# DDS_Tone_Shield.net
KiCad netlist of a schematic drawn in EAGLE
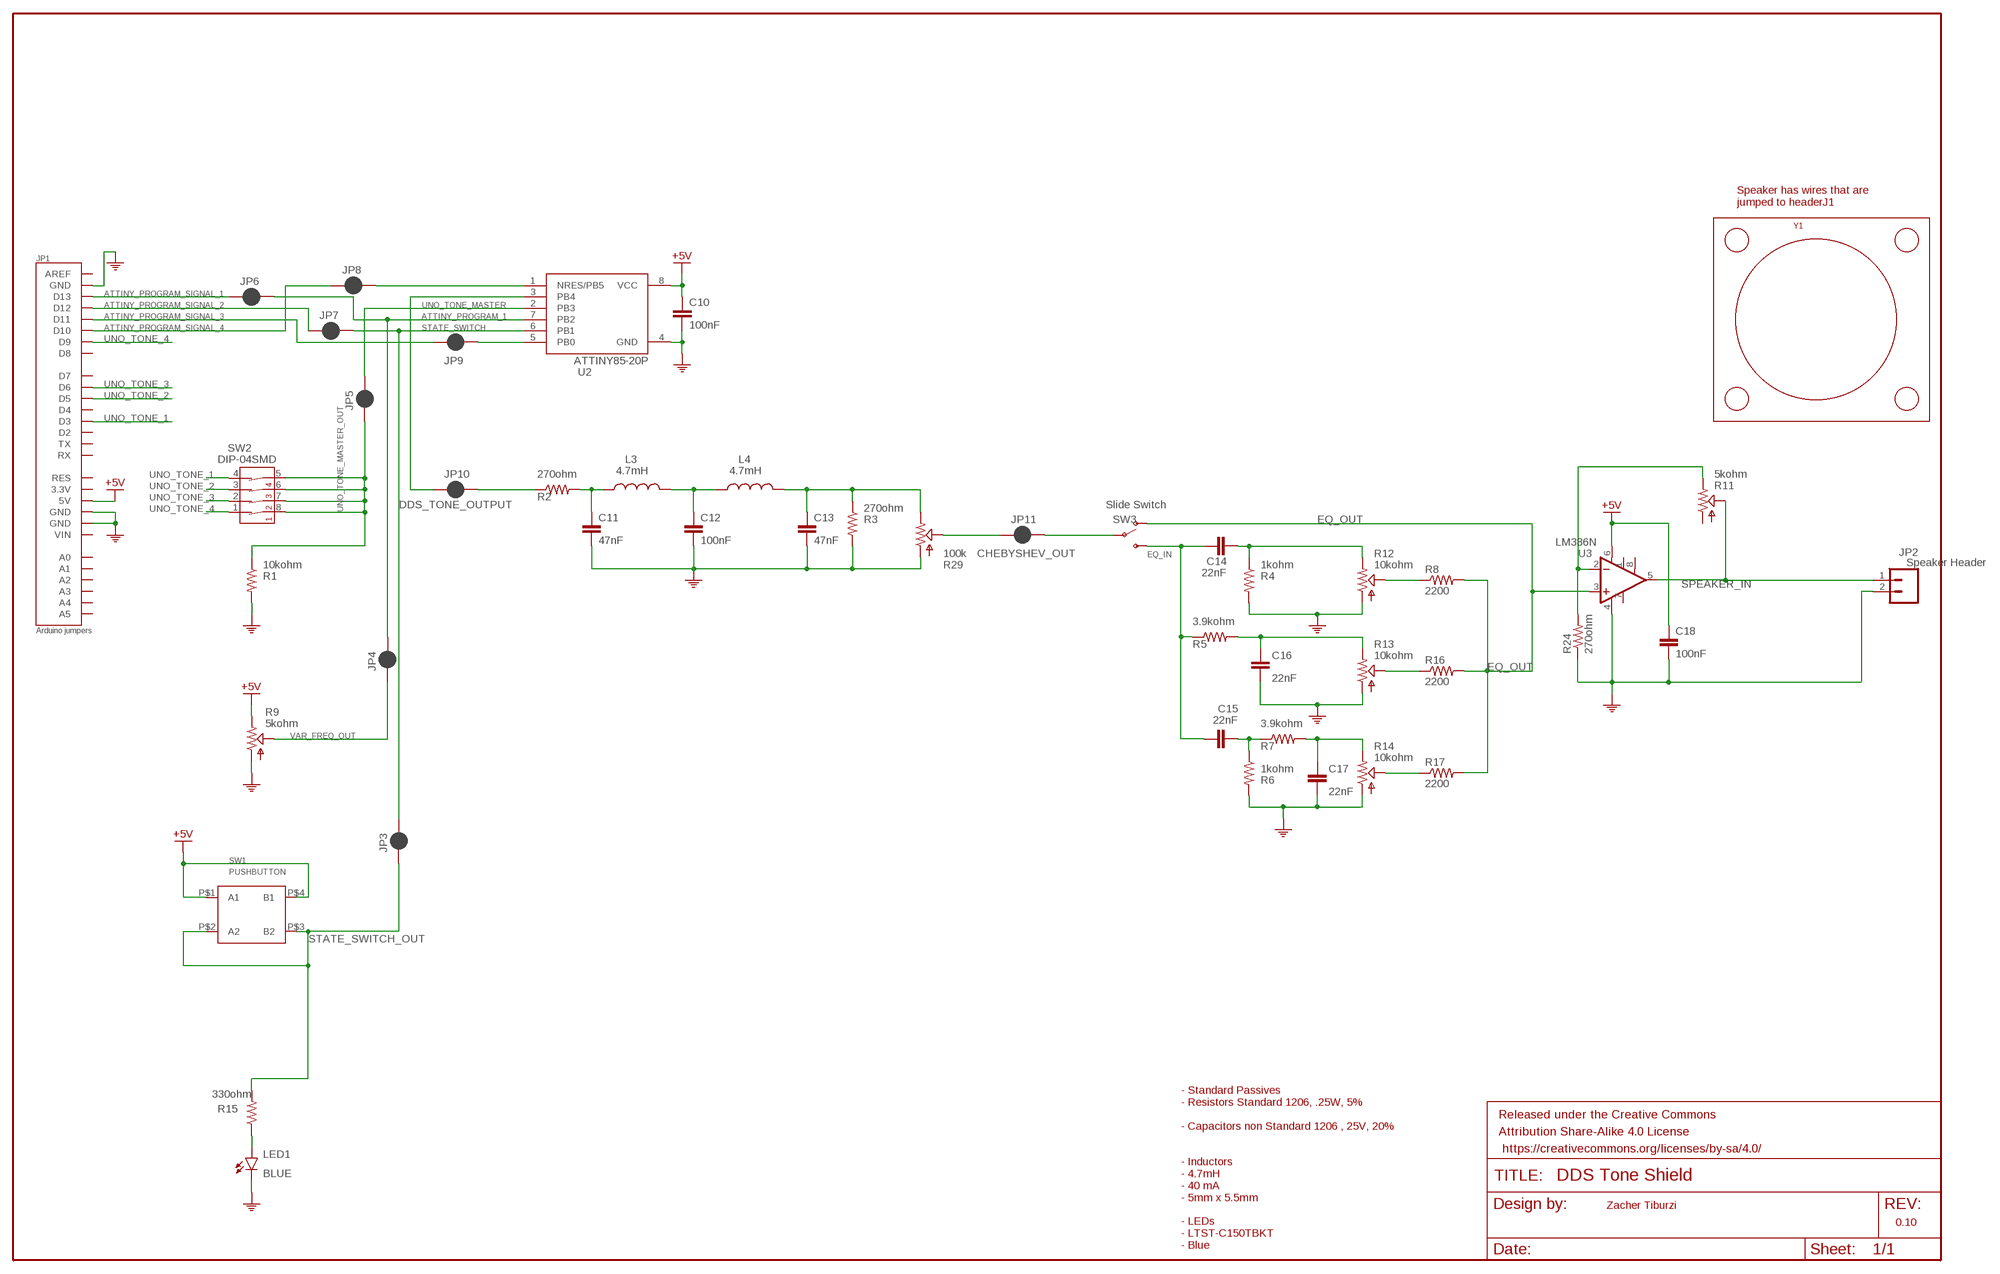
[diagram p0: schematic, sheet 1]

(export (version "E")
  (design (tool "Eeschema 10.0.6"))
  (components
    (comp (ref "C10")
      (value "100nF")
      (footprint "eagle-import:EIA3216")
      (libsource (lib "eagle-import") (part "CAP1206"))
    )
    (comp (ref "C11")
      (value "47nF")
      (footprint "eagle-import:EIA3216")
      (libsource (lib "eagle-import") (part "CAP1206"))
    )
    (comp (ref "C12")
      (value "100nF")
      (footprint "eagle-import:EIA3216")
      (libsource (lib "eagle-import") (part "CAP1206"))
    )
    (comp (ref "C13")
      (value "47nF")
      (footprint "eagle-import:EIA3216")
      (libsource (lib "eagle-import") (part "CAP1206"))
    )
    (comp (ref "C14")
      (value "22nF")
      (footprint "eagle-import:EIA3216")
      (libsource (lib "eagle-import") (part "CAP1206"))
    )
    (comp (ref "C15")
      (value "22nF")
      (footprint "eagle-import:EIA3216")
      (libsource (lib "eagle-import") (part "CAP1206"))
    )
    (comp (ref "C16")
      (value "22nF")
      (footprint "eagle-import:EIA3216")
      (libsource (lib "eagle-import") (part "CAP1206"))
    )
    (comp (ref "C17")
      (value "22nF")
      (footprint "eagle-import:EIA3216")
      (libsource (lib "eagle-import") (part "CAP1206"))
    )
    (comp (ref "C18")
      (value "100nF")
      (footprint "eagle-import:EIA3216")
      (libsource (lib "eagle-import") (part "CAP1206"))
    )
    (comp (ref "FRAME2")
      (value "FRAME-LEDGER")
      (footprint "eagle-import:CREATIVE_COMMONS")
      (libsource (lib "eagle-import") (part "FRAME-LEDGER"))
    )
    (comp (ref "JP1")
      (value "Arduino jumpers")
      (footprint "eagle-import:DUEMILANOVE_SHIELD")
      (libsource (lib "eagle-import") (part "ARDUINO_SHIELD"))
    )
    (comp (ref "JP2")
      (value "Speaker Header")
      (footprint "eagle-import:1X02")
      (libsource (lib "eagle-import") (part "CONN_02"))
    )
    (comp (ref "JP3")
      (value "JUMPER-SMT_2_NC_PASTE_SILK")
      (footprint "eagle-import:SMT-JUMPER_2_NC_PASTE_SILK")
      (libsource (lib "eagle-import") (part "JUMPER-SMT_2_NC_PASTE_SILK"))
    )
    (comp (ref "JP4")
      (value "JUMPER-SMT_2_NC_PASTE_SILK")
      (footprint "eagle-import:SMT-JUMPER_2_NC_PASTE_SILK")
      (libsource (lib "eagle-import") (part "JUMPER-SMT_2_NC_PASTE_SILK"))
    )
    (comp (ref "JP5")
      (value "JUMPER-SMT_2_NC_PASTE_SILK")
      (footprint "eagle-import:SMT-JUMPER_2_NC_PASTE_SILK")
      (libsource (lib "eagle-import") (part "JUMPER-SMT_2_NC_PASTE_SILK"))
    )
    (comp (ref "JP6")
      (value "JUMPER-SMT_2_NC_PASTE_SILK")
      (footprint "eagle-import:SMT-JUMPER_2_NC_PASTE_SILK")
      (libsource (lib "eagle-import") (part "JUMPER-SMT_2_NC_PASTE_SILK"))
    )
    (comp (ref "JP7")
      (value "JUMPER-SMT_2_NC_PASTE_SILK")
      (footprint "eagle-import:SMT-JUMPER_2_NC_PASTE_SILK")
      (libsource (lib "eagle-import") (part "JUMPER-SMT_2_NC_PASTE_SILK"))
    )
    (comp (ref "JP8")
      (value "JUMPER-SMT_2_NC_PASTE_SILK")
      (footprint "eagle-import:SMT-JUMPER_2_NC_PASTE_SILK")
      (libsource (lib "eagle-import") (part "JUMPER-SMT_2_NC_PASTE_SILK"))
    )
    (comp (ref "JP9")
      (value "JUMPER-SMT_2_NC_PASTE_SILK")
      (footprint "eagle-import:SMT-JUMPER_2_NC_PASTE_SILK")
      (libsource (lib "eagle-import") (part "JUMPER-SMT_2_NC_PASTE_SILK"))
    )
    (comp (ref "JP10")
      (value "JUMPER-SMT_2_NC_PASTE_SILK")
      (footprint "eagle-import:SMT-JUMPER_2_NC_PASTE_SILK")
      (libsource (lib "eagle-import") (part "JUMPER-SMT_2_NC_PASTE_SILK"))
    )
    (comp (ref "JP11")
      (value "JUMPER-SMT_2_NC_PASTE_SILK")
      (footprint "eagle-import:SMT-JUMPER_2_NC_PASTE_SILK")
      (libsource (lib "eagle-import") (part "JUMPER-SMT_2_NC_PASTE_SILK"))
    )
    (comp (ref "L3")
      (value "4.7mH")
      (footprint "eagle-import:SDR0503-472JL")
      (libsource (lib "eagle-import") (part "INDUCTOR_"))
    )
    (comp (ref "L4")
      (value "4.7mH")
      (footprint "eagle-import:SDR0503-472JL")
      (libsource (lib "eagle-import") (part "INDUCTOR_"))
    )
    (comp (ref "LED1")
      (value "BLUE")
      (footprint "eagle-import:LED-1206")
      (libsource (lib "eagle-import") (part "LED-BLUE1206"))
    )
    (comp (ref "R1")
      (value "10kohm")
      (footprint "eagle-import:1206")
      (libsource (lib "eagle-import") (part "RESISTOR1206"))
    )
    (comp (ref "R2")
      (value "270ohm")
      (footprint "eagle-import:1206")
      (libsource (lib "eagle-import") (part "RESISTOR1206"))
    )
    (comp (ref "R3")
      (value "270ohm")
      (footprint "eagle-import:1206")
      (libsource (lib "eagle-import") (part "RESISTOR1206"))
    )
    (comp (ref "R4")
      (value "1kohm")
      (footprint "eagle-import:1206")
      (libsource (lib "eagle-import") (part "RESISTOR1206"))
    )
    (comp (ref "R5")
      (value "3.9kohm")
      (footprint "eagle-import:1206")
      (libsource (lib "eagle-import") (part "RESISTOR1206"))
    )
    (comp (ref "R6")
      (value "1kohm")
      (footprint "eagle-import:1206")
      (libsource (lib "eagle-import") (part "RESISTOR1206"))
    )
    (comp (ref "R7")
      (value "3.9kohm")
      (footprint "eagle-import:1206")
      (libsource (lib "eagle-import") (part "RESISTOR1206"))
    )
    (comp (ref "R8")
      (value "2200")
      (footprint "eagle-import:1206")
      (libsource (lib "eagle-import") (part "RESISTOR1206"))
    )
    (comp (ref "R9")
      (value "5kohm")
      (footprint "eagle-import:RK09K_RK09D_SERIES")
      (libsource (lib "eagle-import") (part "POT1"))
    )
    (comp (ref "R11")
      (value "5kohm")
      (footprint "eagle-import:RK09K_RK09D_SERIES")
      (libsource (lib "eagle-import") (part "POT1"))
    )
    (comp (ref "R12")
      (value "10kohm")
      (footprint "eagle-import:RK09K_RK09D_SERIES")
      (libsource (lib "eagle-import") (part "POT1"))
    )
    (comp (ref "R13")
      (value "10kohm")
      (footprint "eagle-import:RK09K_RK09D_SERIES")
      (libsource (lib "eagle-import") (part "POT1"))
    )
    (comp (ref "R14")
      (value "10kohm")
      (footprint "eagle-import:RK09K_RK09D_SERIES")
      (libsource (lib "eagle-import") (part "POT1"))
    )
    (comp (ref "R15")
      (value "330ohm")
      (footprint "eagle-import:1206")
      (libsource (lib "eagle-import") (part "RESISTOR1206"))
    )
    (comp (ref "R16")
      (value "2200")
      (footprint "eagle-import:1206")
      (libsource (lib "eagle-import") (part "RESISTOR1206"))
    )
    (comp (ref "R17")
      (value "2200")
      (footprint "eagle-import:1206")
      (libsource (lib "eagle-import") (part "RESISTOR1206"))
    )
    (comp (ref "R24")
      (value "270ohm")
      (footprint "eagle-import:1206")
      (libsource (lib "eagle-import") (part "RESISTOR1206"))
    )
    (comp (ref "R29")
      (value "100k")
      (footprint "eagle-import:RK09K_RK09D_SERIES")
      (libsource (lib "eagle-import") (part "POT1"))
    )
    (comp (ref "SW1")
      (value "PUSHBUTTON")
      (footprint "eagle-import:3CSH9_MEC_PUSHBUTTON")
      (libsource (lib "eagle-import") (part "PUSHBUTTON"))
    )
    (comp (ref "SW2")
      (value "DIP-04SMD")
      (footprint "eagle-import:DIPSWITCH-04-SMD")
      (libsource (lib "eagle-import") (part "DIP-04SMD"))
    )
    (comp (ref "SW3")
      (value "Slide Switch")
      (footprint "eagle-import:JS102011SAQN")
      (libsource (lib "eagle-import") (part "SWITCH-SPDT"))
    )
    (comp (ref "U2")
      (value "ATTINY85-20P")
      (footprint "eagle-import:PDIP08_300MIL")
      (libsource (lib "eagle-import") (part "ATTINY85P-20"))
    )
    (comp (ref "U3")
      (value "LM386N")
      (footprint "eagle-import:DIP08")
      (libsource (lib "eagle-import") (part "LM386"))
    )
    (comp (ref "Y1")
      (value "Speaker")
      (footprint "eagle-import:CSS-40408N")
      (libsource (lib "eagle-import") (part "SPEAKER"))
    )
  )
  (nets
    (net (code "1") (name "/ATTINY_PROGRAM_1") (class "Default")
      (node (ref "JP4") (pin "2") (pinfunction "2_2") (pintype "passive"))
      (node (ref "JP6") (pin "2") (pinfunction "2_2") (pintype "passive"))
      (node (ref "U2") (pin "7") (pinfunction "PB2_7") (pintype "bidirectional"))
    )
    (net (code "2") (name "/ATTINY_PROGRAM_SIGNAL_1") (class "Default")
      (node (ref "JP1") (pin "D13") (pinfunction "D13_D13") (pintype "bidirectional"))
      (node (ref "JP6") (pin "1") (pinfunction "1_1") (pintype "passive"))
    )
    (net (code "3") (name "/ATTINY_PROGRAM_SIGNAL_2") (class "Default")
      (node (ref "JP1") (pin "D12") (pinfunction "D12_D12") (pintype "bidirectional"))
      (node (ref "JP7") (pin "1") (pinfunction "1_1") (pintype "passive"))
    )
    (net (code "4") (name "/ATTINY_PROGRAM_SIGNAL_3") (class "Default")
      (node (ref "JP1") (pin "D11") (pinfunction "D11_D11") (pintype "bidirectional"))
      (node (ref "JP9") (pin "1") (pinfunction "1_1") (pintype "passive"))
    )
    (net (code "5") (name "/ATTINY_PROGRAM_SIGNAL_4") (class "Default")
      (node (ref "JP1") (pin "D10") (pinfunction "D10_D10") (pintype "bidirectional"))
      (node (ref "JP8") (pin "1") (pinfunction "1_1") (pintype "passive"))
    )
    (net (code "6") (name "/CHEBYSHEV_OUT") (class "Default")
      (node (ref "JP11") (pin "1") (pinfunction "1_1") (pintype "passive"))
      (node (ref "R29") (pin "P$2") (pinfunction "S_P$2") (pintype "passive"))
    )
    (net (code "7") (name "/DDS_TONE_OUTPUT") (class "Default")
      (node (ref "JP10") (pin "1") (pinfunction "1_1") (pintype "passive"))
      (node (ref "U2") (pin "3") (pinfunction "PB4_3") (pintype "bidirectional"))
    )
    (net (code "8") (name "/EQ_IN") (class "Default")
      (node (ref "C14") (pin "A") (pinfunction "1_A") (pintype "passive"))
      (node (ref "C15") (pin "A") (pinfunction "1_A") (pintype "passive"))
      (node (ref "R5") (pin "1") (pinfunction "1_1") (pintype "passive"))
      (node (ref "SW3") (pin "P$1") (pinfunction "S_P$1") (pintype "passive"))
    )
    (net (code "9") (name "/EQ_OUT") (class "Default")
      (node (ref "R16") (pin "2") (pinfunction "2_2") (pintype "passive"))
      (node (ref "R17") (pin "2") (pinfunction "2_2") (pintype "passive"))
      (node (ref "R8") (pin "2") (pinfunction "2_2") (pintype "passive"))
      (node (ref "SW3") (pin "P$2") (pinfunction "O_P$2") (pintype "passive"))
      (node (ref "U3") (pin "3") (pinfunction "+IN_3") (pintype "input"))
    )
    (net (code "10") (name "/SPEAKER_IN") (class "Default")
      (node (ref "JP2") (pin "1") (pinfunction "1_1") (pintype "passive"))
      (node (ref "R11") (pin "P$2") (pinfunction "S_P$2") (pintype "passive"))
      (node (ref "U3") (pin "5") (pinfunction "OUT_5") (pintype "output"))
    )
    (net (code "11") (name "/STATE_SWITCH") (class "Default")
      (node (ref "JP3") (pin "2") (pinfunction "2_2") (pintype "passive"))
      (node (ref "JP7") (pin "2") (pinfunction "2_2") (pintype "passive"))
      (node (ref "U2") (pin "6") (pinfunction "PB1_6") (pintype "bidirectional"))
    )
    (net (code "12") (name "/STATE_SWITCH_OUT") (class "Default")
      (node (ref "JP3") (pin "1") (pinfunction "1_1") (pintype "passive"))
      (node (ref "R15") (pin "2") (pinfunction "2_2") (pintype "passive"))
      (node (ref "SW1") (pin "P$2") (pinfunction "A2_P$2") (pintype "bidirectional"))
      (node (ref "SW1") (pin "P$3") (pinfunction "B2_P$3") (pintype "bidirectional"))
    )
    (net (code "13") (name "/UNO_TONE_1") (class "Default")
      (node (ref "JP1") (pin "D3") (pinfunction "D3_D3") (pintype "bidirectional"))
      (node (ref "SW2") (pin "4") (pinfunction "4A_4") (pintype "bidirectional"))
    )
    (net (code "14") (name "/UNO_TONE_2") (class "Default")
      (node (ref "JP1") (pin "D5") (pinfunction "D5_D5") (pintype "bidirectional"))
      (node (ref "SW2") (pin "3") (pinfunction "3A_3") (pintype "bidirectional"))
    )
    (net (code "15") (name "/UNO_TONE_3") (class "Default")
      (node (ref "JP1") (pin "D6") (pinfunction "D6_D6") (pintype "bidirectional"))
      (node (ref "SW2") (pin "2") (pinfunction "2A_2") (pintype "bidirectional"))
    )
    (net (code "16") (name "/UNO_TONE_4") (class "Default")
      (node (ref "JP1") (pin "D9") (pinfunction "D9_D9") (pintype "bidirectional"))
      (node (ref "SW2") (pin "1") (pinfunction "1A_1") (pintype "bidirectional"))
    )
    (net (code "17") (name "/UNO_TONE_MASTER") (class "Default")
      (node (ref "JP5") (pin "2") (pinfunction "2_2") (pintype "passive"))
      (node (ref "U2") (pin "2") (pinfunction "PB3_2") (pintype "bidirectional"))
    )
    (net (code "18") (name "/UNO_TONE_MASTER_OUT") (class "Default")
      (node (ref "JP5") (pin "1") (pinfunction "1_1") (pintype "passive"))
      (node (ref "R1") (pin "1") (pinfunction "1_1") (pintype "passive"))
      (node (ref "SW2") (pin "5") (pinfunction "4B_5") (pintype "bidirectional"))
      (node (ref "SW2") (pin "6") (pinfunction "3B_6") (pintype "bidirectional"))
      (node (ref "SW2") (pin "7") (pinfunction "2B_7") (pintype "bidirectional"))
      (node (ref "SW2") (pin "8") (pinfunction "1B_8") (pintype "bidirectional"))
    )
    (net (code "19") (name "/VAR_FREQ_OUT") (class "Default")
      (node (ref "JP4") (pin "1") (pinfunction "1_1") (pintype "passive"))
      (node (ref "R9") (pin "P$2") (pinfunction "S_P$2") (pintype "passive"))
    )
    (net (code "20") (name "5V") (class "Default")
      (node (ref "C10") (pin "A") (pinfunction "1_A") (pintype "passive"))
      (node (ref "C18") (pin "A") (pinfunction "1_A") (pintype "passive"))
      (node (ref "JP1") (pin "5V") (pinfunction "5V_5V") (pintype "bidirectional"))
      (node (ref "R9") (pin "P$3") (pinfunction "E_P$3") (pintype "passive"))
      (node (ref "SW1") (pin "P$1") (pinfunction "A1_P$1") (pintype "bidirectional"))
      (node (ref "SW1") (pin "P$4") (pinfunction "B1_P$4") (pintype "bidirectional"))
      (node (ref "U2") (pin "8") (pinfunction "VCC_8") (pintype "power_in"))
      (node (ref "U3") (pin "6") (pinfunction "V+_6") (pintype "power_in"))
    )
    (net (code "21") (name "GND_US") (class "Default")
      (node (ref "C10") (pin "C") (pinfunction "2_C") (pintype "passive"))
      (node (ref "C11") (pin "C") (pinfunction "2_C") (pintype "passive"))
      (node (ref "C12") (pin "C") (pinfunction "2_C") (pintype "passive"))
      (node (ref "C13") (pin "C") (pinfunction "2_C") (pintype "passive"))
      (node (ref "C16") (pin "C") (pinfunction "2_C") (pintype "passive"))
      (node (ref "C17") (pin "C") (pinfunction "2_C") (pintype "passive"))
      (node (ref "C18") (pin "C") (pinfunction "2_C") (pintype "passive"))
      (node (ref "JP1") (pin "GND@0") (pinfunction "GND_GND@0") (pintype "bidirectional"))
      (node (ref "JP1") (pin "GND@1") (pinfunction "GND_GND@1") (pintype "bidirectional"))
      (node (ref "JP1") (pin "GND@2") (pinfunction "GND_GND@2") (pintype "bidirectional"))
      (node (ref "JP2") (pin "2") (pinfunction "2_2") (pintype "passive"))
      (node (ref "LED1") (pin "C") (pinfunction "C_C") (pintype "passive"))
      (node (ref "R1") (pin "2") (pinfunction "2_2") (pintype "passive"))
      (node (ref "R12") (pin "P$1") (pinfunction "A_P$1") (pintype "passive"))
      (node (ref "R13") (pin "P$1") (pinfunction "A_P$1") (pintype "passive"))
      (node (ref "R14") (pin "P$1") (pinfunction "A_P$1") (pintype "passive"))
      (node (ref "R24") (pin "1") (pinfunction "1_1") (pintype "passive"))
      (node (ref "R29") (pin "P$1") (pinfunction "A_P$1") (pintype "passive"))
      (node (ref "R3") (pin "2") (pinfunction "2_2") (pintype "passive"))
      (node (ref "R4") (pin "2") (pinfunction "2_2") (pintype "passive"))
      (node (ref "R6") (pin "2") (pinfunction "2_2") (pintype "passive"))
      (node (ref "R9") (pin "P$1") (pinfunction "A_P$1") (pintype "passive"))
      (node (ref "U2") (pin "4") (pinfunction "GND_4") (pintype "power_in"))
      (node (ref "U3") (pin "4") (pinfunction "V-_4") (pintype "power_in"))
    )
    (net (code "22") (name "Net-(C11-1)") (class "Default")
      (node (ref "C11") (pin "A") (pinfunction "1_A") (pintype "passive"))
      (node (ref "L3") (pin "P$1") (pinfunction "1_P$1") (pintype "passive"))
      (node (ref "R2") (pin "2") (pinfunction "2_2") (pintype "passive"))
    )
    (net (code "23") (name "Net-(C12-1)") (class "Default")
      (node (ref "C12") (pin "A") (pinfunction "1_A") (pintype "passive"))
      (node (ref "L3") (pin "P$2") (pinfunction "2_P$2") (pintype "passive"))
      (node (ref "L4") (pin "P$1") (pinfunction "1_P$1") (pintype "passive"))
    )
    (net (code "24") (name "Net-(C13-1)") (class "Default")
      (node (ref "C13") (pin "A") (pinfunction "1_A") (pintype "passive"))
      (node (ref "L4") (pin "P$2") (pinfunction "2_P$2") (pintype "passive"))
      (node (ref "R29") (pin "P$3") (pinfunction "E_P$3") (pintype "passive"))
      (node (ref "R3") (pin "1") (pinfunction "1_1") (pintype "passive"))
    )
    (net (code "25") (name "Net-(C14-2)") (class "Default")
      (node (ref "C14") (pin "C") (pinfunction "2_C") (pintype "passive"))
      (node (ref "R12") (pin "P$3") (pinfunction "E_P$3") (pintype "passive"))
      (node (ref "R4") (pin "1") (pinfunction "1_1") (pintype "passive"))
    )
    (net (code "26") (name "Net-(C15-2)") (class "Default")
      (node (ref "C15") (pin "C") (pinfunction "2_C") (pintype "passive"))
      (node (ref "R6") (pin "1") (pinfunction "1_1") (pintype "passive"))
      (node (ref "R7") (pin "1") (pinfunction "1_1") (pintype "passive"))
    )
    (net (code "27") (name "Net-(C16-1)") (class "Default")
      (node (ref "C16") (pin "A") (pinfunction "1_A") (pintype "passive"))
      (node (ref "R13") (pin "P$3") (pinfunction "E_P$3") (pintype "passive"))
      (node (ref "R5") (pin "2") (pinfunction "2_2") (pintype "passive"))
    )
    (net (code "28") (name "Net-(C17-1)") (class "Default")
      (node (ref "C17") (pin "A") (pinfunction "1_A") (pintype "passive"))
      (node (ref "R14") (pin "P$3") (pinfunction "E_P$3") (pintype "passive"))
      (node (ref "R7") (pin "2") (pinfunction "2_2") (pintype "passive"))
    )
    (net (code "29") (name "Net-(JP10-Pad2)") (class "Default")
      (node (ref "JP10") (pin "2") (pinfunction "2_2") (pintype "passive"))
      (node (ref "R2") (pin "1") (pinfunction "1_1") (pintype "passive"))
    )
    (net (code "30") (name "Net-(LED1-PadA)") (class "Default")
      (node (ref "LED1") (pin "A") (pinfunction "A_A") (pintype "passive"))
      (node (ref "R15") (pin "1") (pinfunction "1_1") (pintype "passive"))
    )
    (net (code "31") (name "Net-(R11-E)") (class "Default")
      (node (ref "R11") (pin "P$3") (pinfunction "E_P$3") (pintype "passive"))
      (node (ref "R24") (pin "2") (pinfunction "2_2") (pintype "passive"))
      (node (ref "U3") (pin "2") (pinfunction "-IN_2") (pintype "input"))
    )
    (net (code "32") (name "Net-(R12-S)") (class "Default")
      (node (ref "R12") (pin "P$2") (pinfunction "S_P$2") (pintype "passive"))
      (node (ref "R8") (pin "1") (pinfunction "1_1") (pintype "passive"))
    )
    (net (code "33") (name "Net-(R13-S)") (class "Default")
      (node (ref "R13") (pin "P$2") (pinfunction "S_P$2") (pintype "passive"))
      (node (ref "R16") (pin "1") (pinfunction "1_1") (pintype "passive"))
    )
    (net (code "34") (name "Net-(R14-S)") (class "Default")
      (node (ref "R14") (pin "P$2") (pinfunction "S_P$2") (pintype "passive"))
      (node (ref "R17") (pin "1") (pinfunction "1_1") (pintype "passive"))
    )
    (net (code "35") (name "Net-(SW3-P)") (class "Default")
      (node (ref "JP11") (pin "2") (pinfunction "2_2") (pintype "passive"))
      (node (ref "SW3") (pin "P$3") (pinfunction "P_P$3") (pintype "passive"))
    )
    (net (code "36") (name "Net-(U2-NRES{slash}PB5)") (class "Default")
      (node (ref "JP8") (pin "2") (pinfunction "2_2") (pintype "passive"))
      (node (ref "U2") (pin "1") (pinfunction "NRES/PB5_1") (pintype "bidirectional"))
    )
    (net (code "37") (name "Net-(U2-PB0)") (class "Default")
      (node (ref "JP9") (pin "2") (pinfunction "2_2") (pintype "passive"))
      (node (ref "U2") (pin "5") (pinfunction "PB0_5") (pintype "bidirectional"))
    )
    (net (code "38") (name "unconnected-(JP1-Pad3.3V)") (class "Default")
      (node (ref "JP1") (pin "3.3V") (pinfunction "3.3V_3.3V") (pintype "bidirectional"))
    )
    (net (code "39") (name "unconnected-(JP1-PadA0)") (class "Default")
      (node (ref "JP1") (pin "A0") (pinfunction "A0_A0") (pintype "bidirectional"))
    )
    (net (code "40") (name "unconnected-(JP1-PadA1)") (class "Default")
      (node (ref "JP1") (pin "A1") (pinfunction "A1_A1") (pintype "bidirectional"))
    )
    (net (code "41") (name "unconnected-(JP1-PadA2)") (class "Default")
      (node (ref "JP1") (pin "A2") (pinfunction "A2_A2") (pintype "bidirectional"))
    )
    (net (code "42") (name "unconnected-(JP1-PadA3)") (class "Default")
      (node (ref "JP1") (pin "A3") (pinfunction "A3_A3") (pintype "bidirectional"))
    )
    (net (code "43") (name "unconnected-(JP1-PadA4)") (class "Default")
      (node (ref "JP1") (pin "A4") (pinfunction "A4_A4") (pintype "bidirectional"))
    )
    (net (code "44") (name "unconnected-(JP1-PadA5)") (class "Default")
      (node (ref "JP1") (pin "A5") (pinfunction "A5_A5") (pintype "bidirectional"))
    )
    (net (code "45") (name "unconnected-(JP1-PadAREF)") (class "Default")
      (node (ref "JP1") (pin "AREF") (pinfunction "AREF_AREF") (pintype "bidirectional"))
    )
    (net (code "46") (name "unconnected-(JP1-PadD2)") (class "Default")
      (node (ref "JP1") (pin "D2") (pinfunction "D2_D2") (pintype "bidirectional"))
    )
    (net (code "47") (name "unconnected-(JP1-PadD4)") (class "Default")
      (node (ref "JP1") (pin "D4") (pinfunction "D4_D4") (pintype "bidirectional"))
    )
    (net (code "48") (name "unconnected-(JP1-PadD7)") (class "Default")
      (node (ref "JP1") (pin "D7") (pinfunction "D7_D7") (pintype "bidirectional"))
    )
    (net (code "49") (name "unconnected-(JP1-PadD8)") (class "Default")
      (node (ref "JP1") (pin "D8") (pinfunction "D8_D8") (pintype "bidirectional"))
    )
    (net (code "50") (name "unconnected-(JP1-PadRES)") (class "Default")
      (node (ref "JP1") (pin "RES") (pinfunction "RES_RES") (pintype "bidirectional"))
    )
    (net (code "51") (name "unconnected-(JP1-PadRX)") (class "Default")
      (node (ref "JP1") (pin "RX") (pinfunction "RX_RX") (pintype "bidirectional"))
    )
    (net (code "52") (name "unconnected-(JP1-PadTX)") (class "Default")
      (node (ref "JP1") (pin "TX") (pinfunction "TX_TX") (pintype "bidirectional"))
    )
    (net (code "53") (name "unconnected-(JP1-PadVIN)") (class "Default")
      (node (ref "JP1") (pin "VIN") (pinfunction "VIN_VIN") (pintype "bidirectional"))
    )
    (net (code "54") (name "unconnected-(R11-A-PadP$1)") (class "Default")
      (node (ref "R11") (pin "P$1") (pinfunction "A_P$1") (pintype "passive"))
    )
    (net (code "55") (name "unconnected-(U3-BP-Pad7)") (class "Default")
      (node (ref "U3") (pin "7") (pinfunction "BP_7") (pintype "bidirectional"))
    )
    (net (code "56") (name "unconnected-(U3-GAIN-Pad1)") (class "Default")
      (node (ref "U3") (pin "1") (pinfunction "GAIN_1") (pintype "bidirectional"))
    )
    (net (code "57") (name "unconnected-(U3-GAIN-Pad8)") (class "Default")
      (node (ref "U3") (pin "8") (pinfunction "GAIN_8") (pintype "bidirectional"))
    )
  )
)
